# Interface.net
KiCad netlist of a schematic drawn in Altium Designer
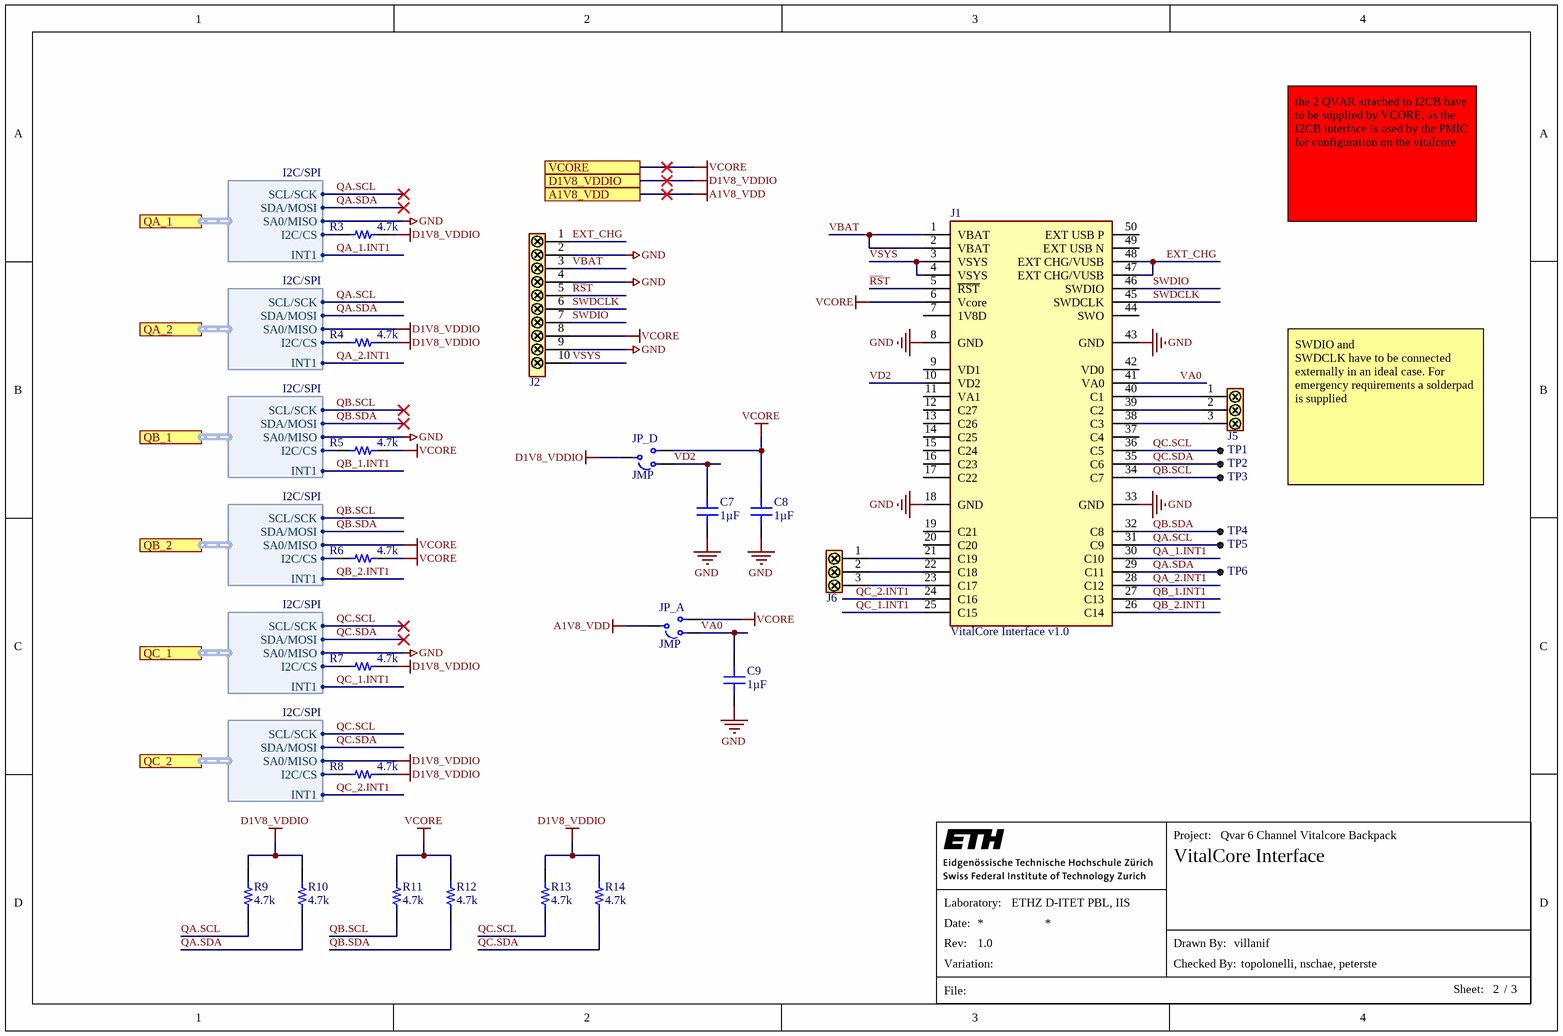
[diagram p0: Interface.SchDoc]

(export (version "E")
  (design (tool "Eeschema 10.0.6"))
  (components
    (comp (ref "C7")
      (value "1µF")
      (footprint "CAP_0201")
      (description "CAP CER 1UF 10V X6S")
      (fields
        (field (name "MANUFACTURER") "Murata")
        (field (name "MANUFACTURER PART NUMBER") "GRM033C81A105ME05D")
      )
      (libsource (lib "6QChan_vitalcore_backpack") (part "CAP_0201_1u_10V"))
    )
    (comp (ref "C8")
      (value "1µF")
      (footprint "CAP_0201")
      (description "CAP CER 1UF 10V X6S")
      (fields
        (field (name "MANUFACTURER") "Murata")
        (field (name "MANUFACTURER PART NUMBER") "GRM033C81A105ME05D")
      )
      (libsource (lib "6QChan_vitalcore_backpack") (part "CAP_0201_1u_10V"))
    )
    (comp (ref "C9")
      (value "1µF")
      (footprint "CAP_0201")
      (description "CAP CER 1UF 10V X6S")
      (fields
        (field (name "MANUFACTURER") "Murata")
        (field (name "MANUFACTURER PART NUMBER") "GRM033C81A105ME05D")
      )
      (libsource (lib "6QChan_vitalcore_backpack") (part "CAP_0201_1u_10V"))
    )
    (comp (ref "J1")
      (value "VitalCore Interface v1.0")
      (footprint "BACKPACK_INTERFACE_V1.0_2mm")
      (fields
        (field (name "MANUFACTURER") "Hirose")
        (field (name "MANUFACTURER PART NUMBER") "DF40C(2.0)-50DS-0.4V(51)")
      )
      (libsource (lib "6QChan_vitalcore_backpack") (part "BACKPACK_INTERFACE_V1.0"))
    )
    (comp (ref "J2")
      (value "FTS-110-01-L-S")
      (footprint "SAMTEC-FTS-110-01-L-S")
      (description "Pinheader 10 pin, 1.27mm")
      (fields (field (name "MANUFACTURER") "Samtec"))
      (libsource (lib "6QChan_vitalcore_backpack") (part "FTS-110-01-L-S"))
    )
    (comp (ref "J5")
      (value "FTS-103-01-L-S")
      (footprint "SAMTEC-FTS-103-01-X-S")
      (description "Pinheader 3 pin, 1.27mm")
      (fields (field (name "MANUFACTURER") "Samtec"))
      (libsource (lib "6QChan_vitalcore_backpack") (part "FTS-103-01-L-S"))
    )
    (comp (ref "J6")
      (value "FTS-103-01-L-S")
      (footprint "SAMTEC-FTS-103-01-X-S")
      (description "Pinheader 3 pin, 1.27mm")
      (fields (field (name "MANUFACTURER") "Samtec"))
      (libsource (lib "") (part "FTS-103-01-L-S_1"))
    )
    (comp (ref "JP_A")
      (value "JMP")
      (footprint "JMP_0201_3way")
      (description "JMP 0201 3W")
      (fields
        (field (name "MANUFACTURER") "Panasonic")
        (field (name "MANUFACTURER PART NUMBER") "ERJ-1GN0R00C")
      )
      (libsource (lib "6QChan_vitalcore_backpack") (part "JMP_0201_3w"))
    )
    (comp (ref "JP_D")
      (value "JMP")
      (footprint "JMP_0201_3way")
      (description "JMP 0201 3W")
      (fields
        (field (name "MANUFACTURER") "Panasonic")
        (field (name "MANUFACTURER PART NUMBER") "ERJ-1GN0R00C")
      )
      (libsource (lib "6QChan_vitalcore_backpack") (part "JMP_0201_3w"))
    )
    (comp (ref "R3")
      (value "4.7k")
      (footprint "RES_0201")
      (description "R 4.7K 1% 50mW 0201")
      (fields
        (field (name "MANUFACTURER") "Panasonic")
        (field (name "MANUFACTURER PART NUMBER") "ERJ-1GNF4701C")
      )
      (libsource (lib "6QChan_vitalcore_backpack") (part "R_0201_4.7K"))
    )
    (comp (ref "R4")
      (value "4.7k")
      (footprint "RES_0201")
      (description "R 4.7K 1% 50mW 0201")
      (fields
        (field (name "MANUFACTURER") "Panasonic")
        (field (name "MANUFACTURER PART NUMBER") "ERJ-1GNF4701C")
      )
      (libsource (lib "6QChan_vitalcore_backpack") (part "R_0201_4.7K"))
    )
    (comp (ref "R5")
      (value "4.7k")
      (footprint "RES_0201")
      (description "R 4.7K 1% 50mW 0201")
      (fields
        (field (name "MANUFACTURER") "Panasonic")
        (field (name "MANUFACTURER PART NUMBER") "ERJ-1GNF4701C")
      )
      (libsource (lib "6QChan_vitalcore_backpack") (part "R_0201_4.7K"))
    )
    (comp (ref "R6")
      (value "4.7k")
      (footprint "RES_0201")
      (description "R 4.7K 1% 50mW 0201")
      (fields
        (field (name "MANUFACTURER") "Panasonic")
        (field (name "MANUFACTURER PART NUMBER") "ERJ-1GNF4701C")
      )
      (libsource (lib "6QChan_vitalcore_backpack") (part "R_0201_4.7K"))
    )
    (comp (ref "R7")
      (value "4.7k")
      (footprint "RES_0201")
      (description "R 4.7K 1% 50mW 0201")
      (fields
        (field (name "MANUFACTURER") "Panasonic")
        (field (name "MANUFACTURER PART NUMBER") "ERJ-1GNF4701C")
      )
      (libsource (lib "6QChan_vitalcore_backpack") (part "R_0201_4.7K"))
    )
    (comp (ref "R8")
      (value "4.7k")
      (footprint "RES_0201")
      (description "R 4.7K 1% 50mW 0201")
      (fields
        (field (name "MANUFACTURER") "Panasonic")
        (field (name "MANUFACTURER PART NUMBER") "ERJ-1GNF4701C")
      )
      (libsource (lib "6QChan_vitalcore_backpack") (part "R_0201_4.7K"))
    )
    (comp (ref "R9")
      (value "4.7k")
      (footprint "RES_0201")
      (description "R 4.7K 1% 50mW 0201")
      (fields
        (field (name "MANUFACTURER") "Panasonic")
        (field (name "MANUFACTURER PART NUMBER") "ERJ-1GNF4701C")
      )
      (libsource (lib "6QChan_vitalcore_backpack") (part "R_0201_4.7K"))
    )
    (comp (ref "R10")
      (value "4.7k")
      (footprint "RES_0201")
      (description "R 4.7K 1% 50mW 0201")
      (fields
        (field (name "MANUFACTURER") "Panasonic")
        (field (name "MANUFACTURER PART NUMBER") "ERJ-1GNF4701C")
      )
      (libsource (lib "6QChan_vitalcore_backpack") (part "R_0201_4.7K"))
    )
    (comp (ref "R11")
      (value "4.7k")
      (footprint "RES_0201")
      (description "R 4.7K 1% 50mW 0201")
      (fields
        (field (name "MANUFACTURER") "Panasonic")
        (field (name "MANUFACTURER PART NUMBER") "ERJ-1GNF4701C")
      )
      (libsource (lib "6QChan_vitalcore_backpack") (part "R_0201_4.7K"))
    )
    (comp (ref "R12")
      (value "4.7k")
      (footprint "RES_0201")
      (description "R 4.7K 1% 50mW 0201")
      (fields
        (field (name "MANUFACTURER") "Panasonic")
        (field (name "MANUFACTURER PART NUMBER") "ERJ-1GNF4701C")
      )
      (libsource (lib "6QChan_vitalcore_backpack") (part "R_0201_4.7K"))
    )
    (comp (ref "R13")
      (value "4.7k")
      (footprint "RES_0201")
      (description "R 4.7K 1% 50mW 0201")
      (fields
        (field (name "MANUFACTURER") "Panasonic")
        (field (name "MANUFACTURER PART NUMBER") "ERJ-1GNF4701C")
      )
      (libsource (lib "6QChan_vitalcore_backpack") (part "R_0201_4.7K"))
    )
    (comp (ref "R14")
      (value "4.7k")
      (footprint "RES_0201")
      (description "R 4.7K 1% 50mW 0201")
      (fields
        (field (name "MANUFACTURER") "Panasonic")
        (field (name "MANUFACTURER PART NUMBER") "ERJ-1GNF4701C")
      )
      (libsource (lib "6QChan_vitalcore_backpack") (part "R_0201_4.7K"))
    )
    (comp (ref "TP1")
      (value "~")
      (footprint "Pad-0.6mm")
      (description "0.6mm SMT Test Pad")
      (libsource (lib "6QChan_vitalcore_backpack") (part "Test Pad"))
    )
    (comp (ref "TP2")
      (value "~")
      (footprint "Pad-0.6mm")
      (description "0.6mm SMT Test Pad")
      (libsource (lib "6QChan_vitalcore_backpack") (part "Test Pad"))
    )
    (comp (ref "TP3")
      (value "~")
      (footprint "Pad-0.6mm")
      (description "0.6mm SMT Test Pad")
      (libsource (lib "6QChan_vitalcore_backpack") (part "Test Pad"))
    )
    (comp (ref "TP4")
      (value "~")
      (footprint "Pad-0.6mm")
      (description "0.6mm SMT Test Pad")
      (libsource (lib "6QChan_vitalcore_backpack") (part "Test Pad"))
    )
    (comp (ref "TP5")
      (value "~")
      (footprint "Pad-0.6mm")
      (description "0.6mm SMT Test Pad")
      (libsource (lib "6QChan_vitalcore_backpack") (part "Test Pad"))
    )
    (comp (ref "TP6")
      (value "~")
      (footprint "Pad-0.6mm")
      (description "0.6mm SMT Test Pad")
      (libsource (lib "6QChan_vitalcore_backpack") (part "Test Pad"))
    )
  )
  (nets
    (net (code "2") (name "/EXT_CHG") (class "Default")
      (node (ref "J1") (pin "47") (pinfunction "EXT_CHG/VUSB_47") (pintype "passive"))
      (node (ref "J1") (pin "48") (pinfunction "EXT_CHG/VUSB_48") (pintype "passive"))
      (node (ref "J2") (pin "1") (pintype "passive"))
    )
    (net (code "3") (name "/QA.SCL") (class "Default")
      (node (ref "J1") (pin "31") (pinfunction "C9_31") (pintype "passive"))
      (node (ref "R9") (pin "2") (pinfunction "2_2") (pintype "passive"))
      (node (ref "TP5") (pin "1") (pinfunction "1_1") (pintype "passive"))
    )
    (net (code "4") (name "/QA.SDA") (class "Default")
      (node (ref "J1") (pin "29") (pinfunction "C11_29") (pintype "passive"))
      (node (ref "R10") (pin "2") (pinfunction "2_2") (pintype "passive"))
      (node (ref "TP6") (pin "1") (pinfunction "1_1") (pintype "passive"))
    )
    (net (code "5") (name "/QA_1.INT1") (class "Default")
      (node (ref "J1") (pin "30") (pinfunction "C10_30") (pintype "passive"))
    )
    (net (code "6") (name "/QA_2.INT1") (class "Default")
      (node (ref "J1") (pin "28") (pinfunction "C12_28") (pintype "passive"))
    )
    (net (code "7") (name "/QB.SCL") (class "Default")
      (node (ref "J1") (pin "34") (pinfunction "C7_34") (pintype "passive"))
      (node (ref "R11") (pin "2") (pinfunction "2_2") (pintype "passive"))
      (node (ref "TP3") (pin "1") (pinfunction "1_1") (pintype "passive"))
    )
    (net (code "8") (name "/QB.SDA") (class "Default")
      (node (ref "J1") (pin "32") (pinfunction "C8_32") (pintype "passive"))
      (node (ref "R12") (pin "2") (pinfunction "2_2") (pintype "passive"))
      (node (ref "TP4") (pin "1") (pinfunction "1_1") (pintype "passive"))
    )
    (net (code "9") (name "/QB_1.INT1") (class "Default")
      (node (ref "J1") (pin "27") (pinfunction "C13_27") (pintype "passive"))
    )
    (net (code "10") (name "/QB_2.INT1") (class "Default")
      (node (ref "J1") (pin "26") (pinfunction "C14_26") (pintype "passive"))
    )
    (net (code "11") (name "/QC.SCL") (class "Default")
      (node (ref "J1") (pin "36") (pinfunction "C5_36") (pintype "passive"))
      (node (ref "R13") (pin "2") (pinfunction "2_2") (pintype "passive"))
      (node (ref "TP1") (pin "1") (pinfunction "1_1") (pintype "passive"))
    )
    (net (code "12") (name "/QC.SDA") (class "Default")
      (node (ref "J1") (pin "35") (pinfunction "C6_35") (pintype "passive"))
      (node (ref "R14") (pin "2") (pinfunction "2_2") (pintype "passive"))
      (node (ref "TP2") (pin "1") (pinfunction "1_1") (pintype "passive"))
    )
    (net (code "13") (name "/QC_1.INT1") (class "Default")
      (node (ref "J1") (pin "25") (pinfunction "C15_25") (pintype "passive"))
    )
    (net (code "14") (name "/QC_2.INT1") (class "Default")
      (node (ref "J1") (pin "24") (pinfunction "C16_24") (pintype "passive"))
    )
    (net (code "15") (name "/SWDCLK") (class "Default")
      (node (ref "J1") (pin "45") (pinfunction "SWDCLK_45") (pintype "passive"))
      (node (ref "J2") (pin "6") (pintype "passive"))
    )
    (net (code "16") (name "/SWDIO") (class "Default")
      (node (ref "J1") (pin "46") (pinfunction "SWDIO_46") (pintype "passive"))
      (node (ref "J2") (pin "7") (pintype "passive"))
    )
    (net (code "17") (name "/VA0") (class "Default")
      (node (ref "C9") (pin "1") (pinfunction "1_1") (pintype "passive"))
      (node (ref "J1") (pin "41") (pinfunction "VA0_41") (pintype "passive"))
      (node (ref "JP_A") (pin "1") (pinfunction "1_1") (pintype "passive"))
    )
    (net (code "18") (name "/VBAT") (class "Default")
      (node (ref "J1") (pin "1") (pinfunction "VBAT_1") (pintype "passive"))
      (node (ref "J1") (pin "2") (pinfunction "VBAT_2") (pintype "passive"))
      (node (ref "J2") (pin "3") (pintype "passive"))
    )
    (net (code "19") (name "/VD2") (class "Default")
      (node (ref "C7") (pin "1") (pinfunction "1_1") (pintype "passive"))
      (node (ref "J1") (pin "10") (pinfunction "VD2_10") (pintype "passive"))
      (node (ref "JP_D") (pin "1") (pinfunction "1_1") (pintype "passive"))
    )
    (net (code "20") (name "/VSYS") (class "Default")
      (node (ref "J1") (pin "3") (pinfunction "VSYS_3") (pintype "passive"))
      (node (ref "J1") (pin "4") (pinfunction "VSYS_4") (pintype "passive"))
      (node (ref "J2") (pin "10") (pintype "passive"))
    )
    (net (code "22") (name "/~{RS}T") (class "Default")
      (node (ref "J1") (pin "5") (pinfunction "~{RST}_5") (pintype "passive"))
      (node (ref "J2") (pin "5") (pintype "passive"))
    )
    (net (code "23") (name "A1V8_VDD") (class "Default")
      (node (ref "JP_A") (pin "2") (pinfunction "2_2") (pintype "passive"))
    )
    (net (code "24") (name "D1V8_VDDIO") (class "Default")
      (node (ref "JP_D") (pin "2") (pinfunction "2_2") (pintype "passive"))
      (node (ref "R10") (pin "1") (pinfunction "1_1") (pintype "passive"))
      (node (ref "R13") (pin "1") (pinfunction "1_1") (pintype "passive"))
      (node (ref "R14") (pin "1") (pinfunction "1_1") (pintype "passive"))
      (node (ref "R3") (pin "1") (pinfunction "1_1") (pintype "passive"))
      (node (ref "R4") (pin "1") (pinfunction "1_1") (pintype "passive"))
      (node (ref "R7") (pin "1") (pinfunction "1_1") (pintype "passive"))
      (node (ref "R8") (pin "1") (pinfunction "1_1") (pintype "passive"))
      (node (ref "R9") (pin "1") (pinfunction "1_1") (pintype "passive"))
    )
    (net (code "25") (name "GND") (class "Default")
      (node (ref "C7") (pin "2") (pinfunction "2_2") (pintype "passive"))
      (node (ref "C8") (pin "2") (pinfunction "2_2") (pintype "passive"))
      (node (ref "C9") (pin "2") (pinfunction "2_2") (pintype "passive"))
      (node (ref "J1") (pin "18") (pinfunction "GND_18") (pintype "passive"))
      (node (ref "J1") (pin "33") (pinfunction "GND_33") (pintype "passive"))
      (node (ref "J1") (pin "43") (pinfunction "GND_43") (pintype "passive"))
      (node (ref "J1") (pin "8") (pinfunction "GND_8") (pintype "passive"))
      (node (ref "J2") (pin "2") (pintype "passive"))
      (node (ref "J2") (pin "4") (pintype "passive"))
      (node (ref "J2") (pin "9") (pintype "passive"))
    )
    (net (code "26") (name "Net-(J1-C1)") (class "Default")
      (node (ref "J1") (pin "40") (pinfunction "C1_40") (pintype "passive"))
      (node (ref "J5") (pin "1") (pintype "passive"))
    )
    (net (code "27") (name "Net-(J1-C2)") (class "Default")
      (node (ref "J1") (pin "39") (pinfunction "C2_39") (pintype "passive"))
      (node (ref "J5") (pin "2") (pintype "passive"))
    )
    (net (code "28") (name "Net-(J1-C3)") (class "Default")
      (node (ref "J1") (pin "38") (pinfunction "C3_38") (pintype "passive"))
      (node (ref "J5") (pin "3") (pintype "passive"))
    )
    (net (code "29") (name "Net-(J1-C17)") (class "Default")
      (node (ref "J1") (pin "23") (pinfunction "C17_23") (pintype "passive"))
      (node (ref "J6") (pin "3") (pintype "passive"))
    )
    (net (code "30") (name "Net-(J1-C18)") (class "Default")
      (node (ref "J1") (pin "22") (pinfunction "C18_22") (pintype "passive"))
      (node (ref "J6") (pin "2") (pintype "passive"))
    )
    (net (code "31") (name "Net-(J1-C19)") (class "Default")
      (node (ref "J1") (pin "21") (pinfunction "C19_21") (pintype "passive"))
      (node (ref "J6") (pin "1") (pintype "passive"))
    )
    (net (code "32") (name "VCORE") (class "Default")
      (node (ref "C8") (pin "1") (pinfunction "1_1") (pintype "passive"))
      (node (ref "J1") (pin "6") (pinfunction "Vcore_6") (pintype "passive"))
      (node (ref "J2") (pin "8") (pintype "passive"))
      (node (ref "JP_A") (pin "3") (pinfunction "3_3") (pintype "passive"))
      (node (ref "JP_D") (pin "3") (pinfunction "3_3") (pintype "passive"))
      (node (ref "R11") (pin "1") (pinfunction "1_1") (pintype "passive"))
      (node (ref "R12") (pin "1") (pinfunction "1_1") (pintype "passive"))
      (node (ref "R5") (pin "1") (pinfunction "1_1") (pintype "passive"))
      (node (ref "R6") (pin "1") (pinfunction "1_1") (pintype "passive"))
    )
    (net (code "33") (name "unconnected-(J1-1V8D-Pad7)") (class "Default")
      (node (ref "J1") (pin "7") (pinfunction "1V8D_7") (pintype "passive"))
    )
    (net (code "34") (name "unconnected-(J1-C4-Pad37)") (class "Default")
      (node (ref "J1") (pin "37") (pinfunction "C4_37") (pintype "passive"))
    )
    (net (code "35") (name "unconnected-(J1-C20-Pad20)") (class "Default")
      (node (ref "J1") (pin "20") (pinfunction "C20_20") (pintype "passive"))
    )
    (net (code "36") (name "unconnected-(J1-C21-Pad19)") (class "Default")
      (node (ref "J1") (pin "19") (pinfunction "C21_19") (pintype "passive"))
    )
    (net (code "37") (name "unconnected-(J1-C22-Pad17)") (class "Default")
      (node (ref "J1") (pin "17") (pinfunction "C22_17") (pintype "passive"))
    )
    (net (code "38") (name "unconnected-(J1-C23-Pad16)") (class "Default")
      (node (ref "J1") (pin "16") (pinfunction "C23_16") (pintype "passive"))
    )
    (net (code "39") (name "unconnected-(J1-C24-Pad15)") (class "Default")
      (node (ref "J1") (pin "15") (pinfunction "C24_15") (pintype "passive"))
    )
    (net (code "40") (name "unconnected-(J1-C25-Pad14)") (class "Default")
      (node (ref "J1") (pin "14") (pinfunction "C25_14") (pintype "passive"))
    )
    (net (code "41") (name "unconnected-(J1-C26-Pad13)") (class "Default")
      (node (ref "J1") (pin "13") (pinfunction "C26_13") (pintype "passive"))
    )
    (net (code "42") (name "unconnected-(J1-C27-Pad12)") (class "Default")
      (node (ref "J1") (pin "12") (pinfunction "C27_12") (pintype "passive"))
    )
    (net (code "43") (name "unconnected-(J1-EXT_USB_N-Pad49)") (class "Default")
      (node (ref "J1") (pin "49") (pinfunction "EXT_USB_N_49") (pintype "passive"))
    )
    (net (code "44") (name "unconnected-(J1-EXT_USB_P-Pad50)") (class "Default")
      (node (ref "J1") (pin "50") (pinfunction "EXT_USB_P_50") (pintype "passive"))
    )
    (net (code "45") (name "unconnected-(J1-SWO-Pad44)") (class "Default")
      (node (ref "J1") (pin "44") (pinfunction "SWO_44") (pintype "passive"))
    )
    (net (code "46") (name "unconnected-(J1-VA1-Pad11)") (class "Default")
      (node (ref "J1") (pin "11") (pinfunction "VA1_11") (pintype "passive"))
    )
    (net (code "47") (name "unconnected-(J1-VD0-Pad42)") (class "Default")
      (node (ref "J1") (pin "42") (pinfunction "VD0_42") (pintype "passive"))
    )
    (net (code "48") (name "unconnected-(J1-VD1-Pad9)") (class "Default")
      (node (ref "J1") (pin "9") (pinfunction "VD1_9") (pintype "passive"))
    )
    (net (code "49") (name "unconnected-(R3-Pad2)") (class "Default")
      (node (ref "R3") (pin "2") (pinfunction "2_2") (pintype "passive"))
    )
    (net (code "50") (name "unconnected-(R4-Pad2)") (class "Default")
      (node (ref "R4") (pin "2") (pinfunction "2_2") (pintype "passive"))
    )
    (net (code "51") (name "unconnected-(R5-Pad2)") (class "Default")
      (node (ref "R5") (pin "2") (pinfunction "2_2") (pintype "passive"))
    )
    (net (code "52") (name "unconnected-(R6-Pad2)") (class "Default")
      (node (ref "R6") (pin "2") (pinfunction "2_2") (pintype "passive"))
    )
    (net (code "53") (name "unconnected-(R7-Pad2)") (class "Default")
      (node (ref "R7") (pin "2") (pinfunction "2_2") (pintype "passive"))
    )
    (net (code "54") (name "unconnected-(R8-Pad2)") (class "Default")
      (node (ref "R8") (pin "2") (pinfunction "2_2") (pintype "passive"))
    )
  )
)
